# M0_Express_eh_shield.net
KiCad netlist of a schematic drawn in EAGLE
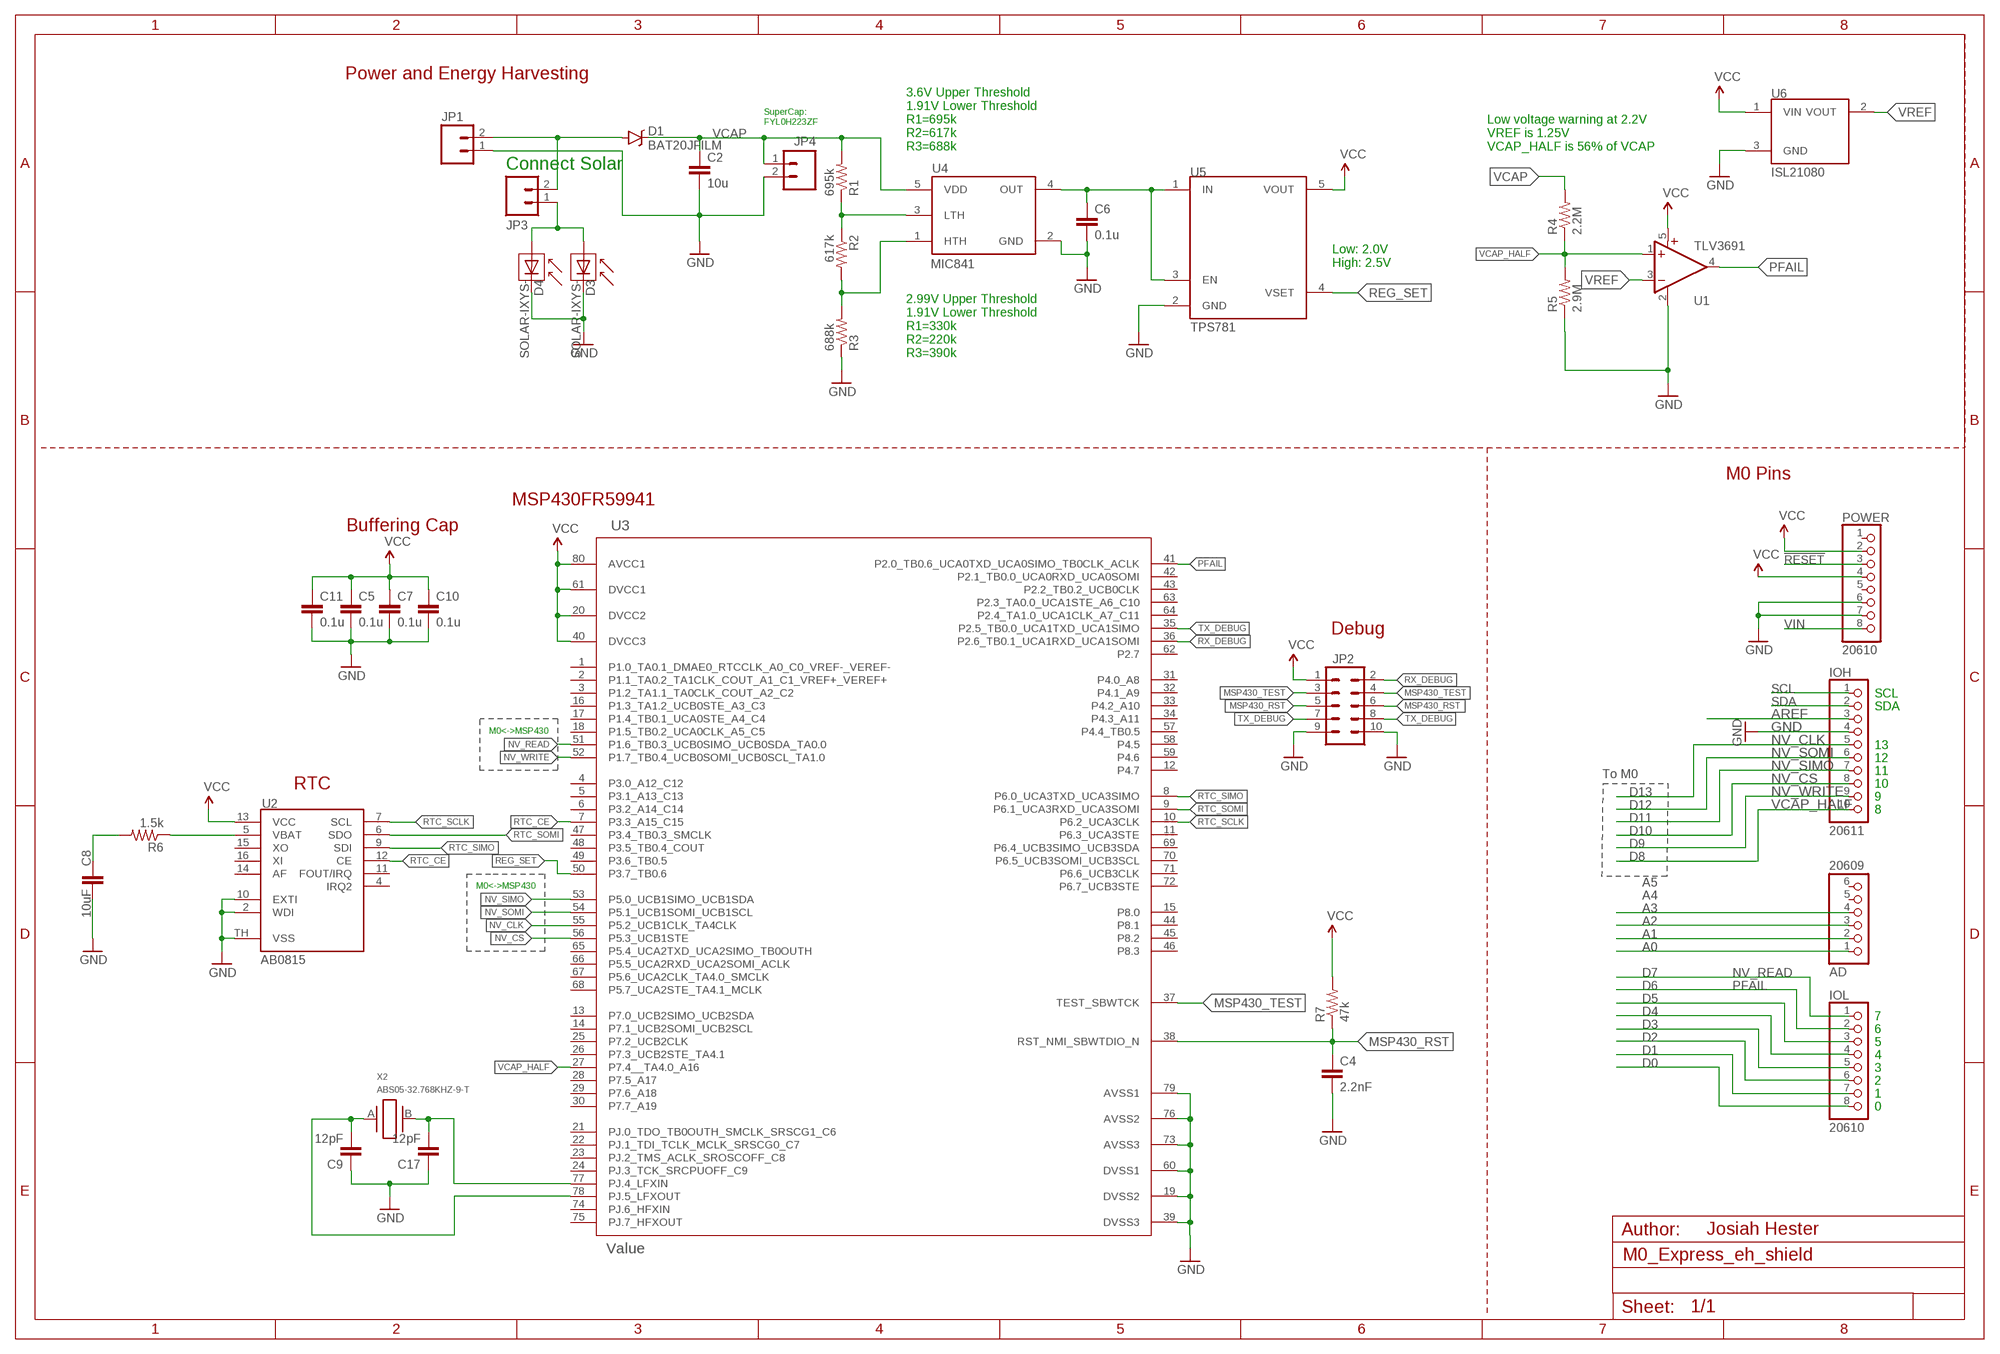
[diagram p0: schematic, sheet 1]

(export (version "E")
  (design (tool "Eeschema 10.0.6"))
  (components
    (comp (ref "AD")
      (value "20609")
      (footprint "eagle-import:1X06_OVALWAVE")
      (libsource (lib "eagle-import") (part "HEADER-1X6OVALWAVE"))
    )
    (comp (ref "C2")
      (value "10u")
      (footprint "eagle-import:0805")
      (libsource (lib "eagle-import") (part "CAP0805"))
    )
    (comp (ref "C4")
      (value "2.2nF")
      (footprint "eagle-import:0603")
      (fields (field (name "MPN") "  06035C222KAT2A"))
      (libsource (lib "eagle-import") (part "C-EU0603"))
    )
    (comp (ref "C5")
      (value "0.1u")
      (footprint "eagle-import:0603")
      (fields (field (name "MPN") "  06035C222KAT2A"))
      (libsource (lib "eagle-import") (part "C-EU0603"))
    )
    (comp (ref "C6")
      (value "0.1u")
      (footprint "eagle-import:0603")
      (fields (field (name "MPN") "  06035C222KAT2A"))
      (libsource (lib "eagle-import") (part "C-EU0603"))
    )
    (comp (ref "C7")
      (value "0.1u")
      (footprint "eagle-import:0603")
      (fields (field (name "MPN") "  06035C222KAT2A"))
      (libsource (lib "eagle-import") (part "C-EU0603"))
    )
    (comp (ref "C8")
      (value "10uF")
      (footprint "eagle-import:0805")
      (fields (field (name "MPN") "0805YD106KAT2A"))
      (libsource (lib "eagle-import") (part "CAP0805"))
    )
    (comp (ref "C9")
      (value "12pF")
      (footprint "eagle-import:0603")
      (fields (field (name "MPN") "CL10C120JB8NNNC"))
      (libsource (lib "eagle-import") (part "C-EU0603"))
    )
    (comp (ref "C10")
      (value "0.1u")
      (footprint "eagle-import:0603")
      (fields (field (name "MPN") "  06035C222KAT2A"))
      (libsource (lib "eagle-import") (part "C-EU0603"))
    )
    (comp (ref "C11")
      (value "0.1u")
      (footprint "eagle-import:0603")
      (fields (field (name "MPN") "  06035C222KAT2A"))
      (libsource (lib "eagle-import") (part "C-EU0603"))
    )
    (comp (ref "C17")
      (value "12pF")
      (footprint "eagle-import:0603")
      (fields (field (name "MPN") "CL10C120JB8NNNC"))
      (libsource (lib "eagle-import") (part "C-EU0603"))
    )
    (comp (ref "D1")
      (value "BAT20JFILM")
      (footprint "eagle-import:SOD-323")
      (libsource (lib "eagle-import") (part "BAT20JFILM"))
    )
    (comp (ref "D3")
      (value "SOLAR-IXYS-")
      (footprint "eagle-import:SOLARBIT-12X1")
      (libsource (lib "eagle-import") (part "SOLAR-IXYS-"))
    )
    (comp (ref "D4")
      (value "SOLAR-IXYS-")
      (footprint "eagle-import:SOLARBIT-12X1")
      (libsource (lib "eagle-import") (part "SOLAR-IXYS-"))
    )
    (comp (ref "IOH")
      (value "20611")
      (footprint "eagle-import:1X10_OVALWAVE")
      (libsource (lib "eagle-import") (part "HEADER-1X10OVALWAVE"))
    )
    (comp (ref "IOL")
      (value "20610")
      (footprint "eagle-import:1X08_OVALWAVE")
      (libsource (lib "eagle-import") (part "HEADER-1X8OVALWAVE"))
    )
    (comp (ref "JP1")
      (value "M02LOCK")
      (footprint "eagle-import:1X02_LOCK")
      (libsource (lib "eagle-import") (part "M02LOCK"))
    )
    (comp (ref "JP2")
      (value "M05X21.27MM")
      (footprint "eagle-import:2X5_1.27MM")
      (libsource (lib "eagle-import") (part "M05X21.27MM"))
    )
    (comp (ref "JP3")
      (value "M02LOCK")
      (footprint "eagle-import:1X02_LOCK")
      (libsource (lib "eagle-import") (part "M02LOCK"))
    )
    (comp (ref "JP4")
      (value "M025MM")
      (footprint "eagle-import:SCREWTERMINAL-5MM-2")
      (libsource (lib "eagle-import") (part "M025MM"))
    )
    (comp (ref "POWER")
      (value "20610")
      (footprint "eagle-import:1X08_OVALWAVE")
      (libsource (lib "eagle-import") (part "HEADER-1X8OVALWAVE"))
    )
    (comp (ref "R1")
      (value "695k")
      (footprint "eagle-import:0603")
      (fields (field (name "MANUFACTURERPARTNUMBER") "RC0603FR-07316KL "))
      (libsource (lib "eagle-import") (part "R-EU0603"))
    )
    (comp (ref "R2")
      (value "617k")
      (footprint "eagle-import:0603")
      (fields (field (name "MANUFACTURERPARTNUMBER") "RC0603FR-07191KL "))
      (libsource (lib "eagle-import") (part "R-EU0603"))
    )
    (comp (ref "R3")
      (value "688k")
      (footprint "eagle-import:0603")
      (fields (field (name "MANUFACTURERPARTNUMBER") "RC0603FR-07499KL"))
      (libsource (lib "eagle-import") (part "R-EU0603"))
    )
    (comp (ref "R4")
      (value "2.2M")
      (footprint "eagle-import:0603")
      (libsource (lib "eagle-import") (part "R-EU0603"))
    )
    (comp (ref "R5")
      (value "2.9M")
      (footprint "eagle-import:0603")
      (libsource (lib "eagle-import") (part "R-EU0603"))
    )
    (comp (ref "R6")
      (value "1.5k")
      (footprint "eagle-import:0603")
      (fields (field (name "MPN") "  CRCW060347K0JNEA"))
      (libsource (lib "eagle-import") (part "R-EU0603"))
    )
    (comp (ref "R7")
      (value "47k")
      (footprint "eagle-import:0603")
      (fields (field (name "MPN") "  CRCW060347K0JNEA"))
      (libsource (lib "eagle-import") (part "R-EU0603"))
    )
    (comp (ref "U1")
      (value "TLV3691")
      (footprint "eagle-import:SC70-5")
      (libsource (lib "eagle-import") (part "TLV3691"))
    )
    (comp (ref "U2")
      (value "AB0815")
      (footprint "eagle-import:QFN16")
      (fields (field (name "MPN") "AB0815-T3"))
      (libsource (lib "eagle-import") (part "AB0815"))
    )
    (comp (ref "U3")
      (value "Value")
      (footprint "eagle-import:PN0080A_N")
      (fields
        (field (name "MANUFACTURER") "Texas Instruments")
        (field (name "PARTNUMBER") "MSP430FR5994IPNR")
      )
      (libsource (lib "eagle-import") (part "MSP430FR5994IPNR"))
    )
    (comp (ref "U4")
      (value "MIC841")
      (footprint "eagle-import:SC70-5")
      (fields (field (name "MPN") "MIC841HYC5-TR"))
      (libsource (lib "eagle-import") (part "MIC841"))
    )
    (comp (ref "U5")
      (value "TPS781")
      (footprint "eagle-import:DCK_R-PDSO-G5")
      (libsource (lib "eagle-import") (part "TPS781"))
    )
    (comp (ref "U6")
      (value "ISL21080")
      (footprint "eagle-import:SOT-23")
      (libsource (lib "eagle-import") (part "ISL21080"))
    )
    (comp (ref "X2")
      (value "ABS05-32.768KHZ-9-T")
      (footprint "eagle-import:ABS05")
      (fields (field (name "MPN") "ABS05-32.768KHZ-9-T "))
      (libsource (lib "eagle-import") (part "ABS05-32.768KHZ-9-T"))
    )
  )
  (nets
    (net (code "1") (name "/A0") (class "Default")
      (node (ref "AD") (pin "1") (pinfunction "1_1") (pintype "passive"))
    )
    (net (code "2") (name "/A1") (class "Default")
      (node (ref "AD") (pin "2") (pinfunction "2_2") (pintype "passive"))
    )
    (net (code "3") (name "/A2") (class "Default")
      (node (ref "AD") (pin "3") (pinfunction "3_3") (pintype "passive"))
    )
    (net (code "4") (name "/A3") (class "Default")
      (node (ref "AD") (pin "4") (pinfunction "4_4") (pintype "passive"))
    )
    (net (code "5") (name "/AREF") (class "Default")
      (node (ref "IOH") (pin "3") (pinfunction "3_3") (pintype "passive"))
    )
    (net (code "6") (name "/D0") (class "Default")
      (node (ref "IOL") (pin "8") (pinfunction "8_8") (pintype "passive"))
    )
    (net (code "7") (name "/D1") (class "Default")
      (node (ref "IOL") (pin "7") (pinfunction "7_7") (pintype "passive"))
    )
    (net (code "8") (name "/D2") (class "Default")
      (node (ref "IOL") (pin "6") (pinfunction "6_6") (pintype "passive"))
    )
    (net (code "9") (name "/D3") (class "Default")
      (node (ref "IOL") (pin "5") (pinfunction "5_5") (pintype "passive"))
    )
    (net (code "10") (name "/D4") (class "Default")
      (node (ref "IOL") (pin "4") (pinfunction "4_4") (pintype "passive"))
    )
    (net (code "11") (name "/D5") (class "Default")
      (node (ref "IOL") (pin "3") (pinfunction "3_3") (pintype "passive"))
    )
    (net (code "12") (name "/SCL") (class "Default")
      (node (ref "IOH") (pin "1") (pinfunction "1_1") (pintype "passive"))
    )
    (net (code "13") (name "/SDA") (class "Default")
      (node (ref "IOH") (pin "2") (pinfunction "2_2") (pintype "passive"))
    )
    (net (code "14") (name "/VIN") (class "Default")
      (node (ref "POWER") (pin "8") (pinfunction "8_8") (pintype "passive"))
    )
    (net (code "15") (name "/~{RESET}") (class "Default")
      (node (ref "POWER") (pin "3") (pinfunction "3_3") (pintype "passive"))
    )
    (net (code "16") (name "GND") (class "Default")
      (node (ref "C10") (pin "2") (pinfunction "2_2") (pintype "passive"))
      (node (ref "C11") (pin "2") (pinfunction "2_2") (pintype "passive"))
      (node (ref "C17") (pin "1") (pinfunction "1_1") (pintype "passive"))
      (node (ref "C2") (pin "2") (pinfunction "2_2") (pintype "passive"))
      (node (ref "C4") (pin "2") (pinfunction "2_2") (pintype "passive"))
      (node (ref "C5") (pin "2") (pinfunction "2_2") (pintype "passive"))
      (node (ref "C6") (pin "2") (pinfunction "2_2") (pintype "passive"))
      (node (ref "C7") (pin "2") (pinfunction "2_2") (pintype "passive"))
      (node (ref "C8") (pin "2") (pinfunction "2_2") (pintype "passive"))
      (node (ref "C9") (pin "1") (pinfunction "1_1") (pintype "passive"))
      (node (ref "D3") (pin "-") (pinfunction "C_-") (pintype "passive"))
      (node (ref "D4") (pin "-") (pinfunction "C_-") (pintype "passive"))
      (node (ref "IOH") (pin "4") (pinfunction "4_4") (pintype "passive"))
      (node (ref "JP1") (pin "1") (pinfunction "1_1") (pintype "passive"))
      (node (ref "JP2") (pin "10") (pinfunction "10_10") (pintype "passive"))
      (node (ref "JP2") (pin "9") (pinfunction "9_9") (pintype "passive"))
      (node (ref "JP4") (pin "2") (pinfunction "2_2") (pintype "passive"))
      (node (ref "POWER") (pin "6") (pinfunction "6_6") (pintype "passive"))
      (node (ref "POWER") (pin "7") (pinfunction "7_7") (pintype "passive"))
      (node (ref "R3") (pin "1") (pinfunction "1_1") (pintype "passive"))
      (node (ref "R5") (pin "1") (pinfunction "1_1") (pintype "passive"))
      (node (ref "U1") (pin "2") (pinfunction "GND_2") (pintype "power_in"))
      (node (ref "U2") (pin "10") (pinfunction "EXTI_10") (pintype "bidirectional"))
      (node (ref "U2") (pin "2") (pinfunction "WDI_2") (pintype "bidirectional"))
      (node (ref "U2") (pin "TH") (pinfunction "VSS_TH") (pintype "bidirectional"))
      (node (ref "U3") (pin "19") (pinfunction "DVSS2_19") (pintype "power_in"))
      (node (ref "U3") (pin "39") (pinfunction "DVSS3_39") (pintype "power_in"))
      (node (ref "U3") (pin "60") (pinfunction "DVSS1_60") (pintype "power_in"))
      (node (ref "U3") (pin "73") (pinfunction "AVSS3_73") (pintype "power_in"))
      (node (ref "U3") (pin "76") (pinfunction "AVSS2_76") (pintype "power_in"))
      (node (ref "U3") (pin "79") (pinfunction "AVSS1_79") (pintype "power_in"))
      (node (ref "U4") (pin "2") (pinfunction "GND_2") (pintype "bidirectional"))
      (node (ref "U5") (pin "2") (pinfunction "GND_2") (pintype "bidirectional"))
      (node (ref "U6") (pin "3") (pinfunction "GND_3") (pintype "bidirectional"))
    )
    (net (code "17") (name "MSP430_RST") (class "Default")
      (node (ref "C4") (pin "1") (pinfunction "1_1") (pintype "passive"))
      (node (ref "JP2") (pin "5") (pinfunction "5_5") (pintype "passive"))
      (node (ref "JP2") (pin "6") (pinfunction "6_6") (pintype "passive"))
      (node (ref "R7") (pin "1") (pinfunction "1_1") (pintype "passive"))
      (node (ref "U3") (pin "38") (pinfunction "RST_NMI_SBWTDIO_N_38") (pintype "bidirectional"))
    )
    (net (code "18") (name "MSP430_TEST") (class "Default")
      (node (ref "JP2") (pin "3") (pinfunction "3_3") (pintype "passive"))
      (node (ref "JP2") (pin "4") (pinfunction "4_4") (pintype "passive"))
      (node (ref "U3") (pin "37") (pinfunction "TEST_SBWTCK_37") (pintype "input"))
    )
    (net (code "19") (name "NV_CLK") (class "Default")
      (node (ref "IOH") (pin "5") (pinfunction "5_5") (pintype "passive"))
      (node (ref "U3") (pin "55") (pinfunction "P5.2_UCB1CLK_TA4CLK_55") (pintype "bidirectional"))
    )
    (net (code "20") (name "NV_CS") (class "Default")
      (node (ref "IOH") (pin "8") (pinfunction "8_8") (pintype "passive"))
      (node (ref "U3") (pin "56") (pinfunction "P5.3_UCB1STE_56") (pintype "bidirectional"))
    )
    (net (code "21") (name "NV_READ") (class "Default")
      (node (ref "IOL") (pin "1") (pinfunction "1_1") (pintype "passive"))
      (node (ref "U3") (pin "51") (pinfunction "P1.6_TB0.3_UCB0SIMO_UCB0SDA_TA0.0_51") (pintype "bidirectional"))
    )
    (net (code "22") (name "NV_SIMO") (class "Default")
      (node (ref "IOH") (pin "7") (pinfunction "7_7") (pintype "passive"))
      (node (ref "U3") (pin "53") (pinfunction "P5.0_UCB1SIMO_UCB1SDA_53") (pintype "bidirectional"))
    )
    (net (code "23") (name "NV_SOMI") (class "Default")
      (node (ref "IOH") (pin "6") (pinfunction "6_6") (pintype "passive"))
      (node (ref "U3") (pin "54") (pinfunction "P5.1_UCB1SOMI_UCB1SCL_54") (pintype "bidirectional"))
    )
    (net (code "24") (name "NV_WRITE") (class "Default")
      (node (ref "IOH") (pin "9") (pinfunction "9_9") (pintype "passive"))
      (node (ref "U3") (pin "52") (pinfunction "P1.7_TB0.4_UCB0SOMI_UCB0SCL_TA1.0_52") (pintype "bidirectional"))
    )
    (net (code "25") (name "Net-(C8-Pad1)") (class "Default")
      (node (ref "C8") (pin "1") (pinfunction "1_1") (pintype "passive"))
      (node (ref "R6") (pin "2") (pinfunction "2_2") (pintype "passive"))
    )
    (net (code "26") (name "Net-(D1-PadA)") (class "Default")
      (node (ref "D1") (pin "A") (pinfunction "A_A") (pintype "passive"))
      (node (ref "JP1") (pin "2") (pinfunction "2_2") (pintype "passive"))
      (node (ref "JP3") (pin "2") (pinfunction "2_2") (pintype "passive"))
    )
    (net (code "27") (name "Net-(D3-A)") (class "Default")
      (node (ref "D3") (pin "+") (pinfunction "A_+") (pintype "passive"))
      (node (ref "D4") (pin "+") (pinfunction "A_+") (pintype "passive"))
      (node (ref "JP3") (pin "1") (pinfunction "1_1") (pintype "passive"))
    )
    (net (code "28") (name "Net-(U2-VBAT)") (class "Default")
      (node (ref "R6") (pin "1") (pinfunction "1_1") (pintype "passive"))
      (node (ref "U2") (pin "5") (pinfunction "VBAT_5") (pintype "bidirectional"))
    )
    (net (code "29") (name "Net-(U3-PJ.4_LFXIN)") (class "Default")
      (node (ref "C17") (pin "2") (pinfunction "2_2") (pintype "passive"))
      (node (ref "U3") (pin "77") (pinfunction "PJ.4_LFXIN_77") (pintype "bidirectional"))
      (node (ref "X2") (pin "B") (pinfunction "2_B") (pintype "bidirectional"))
    )
    (net (code "30") (name "Net-(U3-PJ.5_LFXOUT)") (class "Default")
      (node (ref "C9") (pin "2") (pinfunction "2_2") (pintype "passive"))
      (node (ref "U3") (pin "78") (pinfunction "PJ.5_LFXOUT_78") (pintype "bidirectional"))
      (node (ref "X2") (pin "A") (pinfunction "1_A") (pintype "bidirectional"))
    )
    (net (code "31") (name "Net-(U4-HTH)") (class "Default")
      (node (ref "R2") (pin "2") (pinfunction "2_2") (pintype "passive"))
      (node (ref "R3") (pin "2") (pinfunction "2_2") (pintype "passive"))
      (node (ref "U4") (pin "1") (pinfunction "HTH_1") (pintype "bidirectional"))
    )
    (net (code "32") (name "Net-(U4-LTH)") (class "Default")
      (node (ref "R1") (pin "1") (pinfunction "1_1") (pintype "passive"))
      (node (ref "R2") (pin "1") (pinfunction "1_1") (pintype "passive"))
      (node (ref "U4") (pin "3") (pinfunction "LTH_3") (pintype "bidirectional"))
    )
    (net (code "33") (name "Net-(U4-OUT)") (class "Default")
      (node (ref "C6") (pin "1") (pinfunction "1_1") (pintype "passive"))
      (node (ref "U4") (pin "4") (pinfunction "OUT_4") (pintype "bidirectional"))
      (node (ref "U5") (pin "1") (pinfunction "IN_1") (pintype "bidirectional"))
      (node (ref "U5") (pin "3") (pinfunction "EN_3") (pintype "bidirectional"))
    )
    (net (code "34") (name "PFAIL") (class "Default")
      (node (ref "IOL") (pin "2") (pinfunction "2_2") (pintype "passive"))
      (node (ref "U1") (pin "4") (pinfunction "OUT_4") (pintype "output"))
      (node (ref "U3") (pin "41") (pinfunction "P2.0_TB0.6_UCA0TXD_UCA0SIMO_TB0CLK_ACLK_41") (pintype "bidirectional"))
    )
    (net (code "35") (name "REG_SET") (class "Default")
      (node (ref "U3") (pin "50") (pinfunction "P3.7_TB0.6_50") (pintype "bidirectional"))
      (node (ref "U5") (pin "4") (pinfunction "VSET_4") (pintype "bidirectional"))
    )
    (net (code "36") (name "RTC_CE") (class "Default")
      (node (ref "U2") (pin "12") (pinfunction "CE_12") (pintype "bidirectional"))
      (node (ref "U3") (pin "7") (pinfunction "P3.3_A15_C15_7") (pintype "bidirectional"))
    )
    (net (code "37") (name "RTC_SCLK") (class "Default")
      (node (ref "U2") (pin "7") (pinfunction "SCL_7") (pintype "bidirectional"))
      (node (ref "U3") (pin "10") (pinfunction "P6.2_UCA3CLK_10") (pintype "bidirectional"))
    )
    (net (code "38") (name "RTC_SIMO") (class "Default")
      (node (ref "U2") (pin "9") (pinfunction "SDI_9") (pintype "bidirectional"))
      (node (ref "U3") (pin "8") (pinfunction "P6.0_UCA3TXD_UCA3SIMO_8") (pintype "bidirectional"))
    )
    (net (code "39") (name "RTC_SOMI") (class "Default")
      (node (ref "U2") (pin "6") (pinfunction "SDO_6") (pintype "bidirectional"))
      (node (ref "U3") (pin "9") (pinfunction "P6.1_UCA3RXD_UCA3SOMI_9") (pintype "bidirectional"))
    )
    (net (code "40") (name "RX_DEBUG") (class "Default")
      (node (ref "JP2") (pin "2") (pinfunction "2_2") (pintype "passive"))
      (node (ref "U3") (pin "36") (pinfunction "P2.6_TB0.1_UCA1RXD_UCA1SOMI_36") (pintype "bidirectional"))
    )
    (net (code "41") (name "TX_DEBUG") (class "Default")
      (node (ref "JP2") (pin "7") (pinfunction "7_7") (pintype "passive"))
      (node (ref "JP2") (pin "8") (pinfunction "8_8") (pintype "passive"))
      (node (ref "U3") (pin "35") (pinfunction "P2.5_TB0.0_UCA1TXD_UCA1SIMO_35") (pintype "bidirectional"))
    )
    (net (code "42") (name "VCAP") (class "Default")
      (node (ref "C2") (pin "1") (pinfunction "1_1") (pintype "passive"))
      (node (ref "D1") (pin "C") (pinfunction "C_C") (pintype "passive"))
      (node (ref "JP4") (pin "1") (pinfunction "1_1") (pintype "passive"))
      (node (ref "R1") (pin "2") (pinfunction "2_2") (pintype "passive"))
      (node (ref "R4") (pin "2") (pinfunction "2_2") (pintype "passive"))
      (node (ref "U4") (pin "5") (pinfunction "VDD_5") (pintype "bidirectional"))
    )
    (net (code "43") (name "VCAP_HALF") (class "Default")
      (node (ref "IOH") (pin "10") (pinfunction "10_10") (pintype "passive"))
      (node (ref "R4") (pin "1") (pinfunction "1_1") (pintype "passive"))
      (node (ref "R5") (pin "2") (pinfunction "2_2") (pintype "passive"))
      (node (ref "U1") (pin "1") (pinfunction "+IN_1") (pintype "input"))
      (node (ref "U3") (pin "27") (pinfunction "P7.4__TA4.0_A16_27") (pintype "bidirectional"))
    )
    (net (code "44") (name "VCC") (class "Default")
      (node (ref "C10") (pin "1") (pinfunction "1_1") (pintype "passive"))
      (node (ref "C11") (pin "1") (pinfunction "1_1") (pintype "passive"))
      (node (ref "C5") (pin "1") (pinfunction "1_1") (pintype "passive"))
      (node (ref "C7") (pin "1") (pinfunction "1_1") (pintype "passive"))
      (node (ref "JP2") (pin "1") (pinfunction "1_1") (pintype "passive"))
      (node (ref "POWER") (pin "2") (pinfunction "2_2") (pintype "passive"))
      (node (ref "POWER") (pin "4") (pinfunction "4_4") (pintype "passive"))
      (node (ref "R7") (pin "2") (pinfunction "2_2") (pintype "passive"))
      (node (ref "U1") (pin "5") (pinfunction "V+_5") (pintype "power_in"))
      (node (ref "U2") (pin "13") (pinfunction "VCC_13") (pintype "bidirectional"))
      (node (ref "U3") (pin "20") (pinfunction "DVCC2_20") (pintype "power_in"))
      (node (ref "U3") (pin "40") (pinfunction "DVCC3_40") (pintype "power_in"))
      (node (ref "U3") (pin "61") (pinfunction "DVCC1_61") (pintype "power_in"))
      (node (ref "U3") (pin "80") (pinfunction "AVCC1_80") (pintype "power_in"))
      (node (ref "U5") (pin "5") (pinfunction "VOUT_5") (pintype "bidirectional"))
      (node (ref "U6") (pin "1") (pinfunction "VIN_1") (pintype "bidirectional"))
    )
    (net (code "45") (name "VREF") (class "Default")
      (node (ref "U1") (pin "3") (pinfunction "-IN_3") (pintype "input"))
      (node (ref "U6") (pin "2") (pinfunction "VOUT_2") (pintype "bidirectional"))
    )
    (net (code "46") (name "unconnected-(AD-Pad5)") (class "Default")
      (node (ref "AD") (pin "5") (pinfunction "5_5") (pintype "passive"))
    )
    (net (code "47") (name "unconnected-(AD-Pad6)") (class "Default")
      (node (ref "AD") (pin "6") (pinfunction "6_6") (pintype "passive"))
    )
    (net (code "48") (name "unconnected-(POWER-Pad1)") (class "Default")
      (node (ref "POWER") (pin "1") (pinfunction "1_1") (pintype "passive"))
    )
    (net (code "49") (name "unconnected-(POWER-Pad5)") (class "Default")
      (node (ref "POWER") (pin "5") (pinfunction "5_5") (pintype "passive"))
    )
    (net (code "50") (name "unconnected-(U2-AF-Pad14)") (class "Default")
      (node (ref "U2") (pin "14") (pinfunction "AF_14") (pintype "bidirectional"))
    )
    (net (code "51") (name "unconnected-(U2-FOUT{slash}IRQ-Pad11)") (class "Default")
      (node (ref "U2") (pin "11") (pinfunction "FOUT/IRQ_11") (pintype "bidirectional"))
    )
    (net (code "52") (name "unconnected-(U2-IRQ2-Pad4)") (class "Default")
      (node (ref "U2") (pin "4") (pinfunction "IRQ2_4") (pintype "bidirectional"))
    )
    (net (code "53") (name "unconnected-(U2-XI-Pad16)") (class "Default")
      (node (ref "U2") (pin "16") (pinfunction "XI_16") (pintype "bidirectional"))
    )
    (net (code "54") (name "unconnected-(U2-XO-Pad15)") (class "Default")
      (node (ref "U2") (pin "15") (pinfunction "XO_15") (pintype "bidirectional"))
    )
    (net (code "55") (name "unconnected-(U3-P1.0_TA0.1_DMAE0_RTCCLK_A0_C0_VREF-_VEREF--Pad1)") (class "Default")
      (node (ref "U3") (pin "1") (pinfunction "P1.0_TA0.1_DMAE0_RTCCLK_A0_C0_VREF-_VEREF-_1") (pintype "bidirectional"))
    )
    (net (code "56") (name "unconnected-(U3-P1.1_TA0.2_TA1CLK_COUT_A1_C1_VREF+_VEREF+-Pad2)") (class "Default")
      (node (ref "U3") (pin "2") (pinfunction "P1.1_TA0.2_TA1CLK_COUT_A1_C1_VREF+_VEREF+_2") (pintype "bidirectional"))
    )
    (net (code "57") (name "unconnected-(U3-P1.2_TA1.1_TA0CLK_COUT_A2_C2-Pad3)") (class "Default")
      (node (ref "U3") (pin "3") (pinfunction "P1.2_TA1.1_TA0CLK_COUT_A2_C2_3") (pintype "bidirectional"))
    )
    (net (code "58") (name "unconnected-(U3-P1.3_TA1.2_UCB0STE_A3_C3-Pad16)") (class "Default")
      (node (ref "U3") (pin "16") (pinfunction "P1.3_TA1.2_UCB0STE_A3_C3_16") (pintype "bidirectional"))
    )
    (net (code "59") (name "unconnected-(U3-P1.4_TB0.1_UCA0STE_A4_C4-Pad17)") (class "Default")
      (node (ref "U3") (pin "17") (pinfunction "P1.4_TB0.1_UCA0STE_A4_C4_17") (pintype "bidirectional"))
    )
    (net (code "60") (name "unconnected-(U3-P1.5_TB0.2_UCA0CLK_A5_C5-Pad18)") (class "Default")
      (node (ref "U3") (pin "18") (pinfunction "P1.5_TB0.2_UCA0CLK_A5_C5_18") (pintype "bidirectional"))
    )
    (net (code "61") (name "unconnected-(U3-P2.1_TB0.0_UCA0RXD_UCA0SOMI-Pad42)") (class "Default")
      (node (ref "U3") (pin "42") (pinfunction "P2.1_TB0.0_UCA0RXD_UCA0SOMI_42") (pintype "bidirectional"))
    )
    (net (code "62") (name "unconnected-(U3-P2.2_TB0.2_UCB0CLK-Pad43)") (class "Default")
      (node (ref "U3") (pin "43") (pinfunction "P2.2_TB0.2_UCB0CLK_43") (pintype "bidirectional"))
    )
    (net (code "63") (name "unconnected-(U3-P2.3_TA0.0_UCA1STE_A6_C10-Pad63)") (class "Default")
      (node (ref "U3") (pin "63") (pinfunction "P2.3_TA0.0_UCA1STE_A6_C10_63") (pintype "bidirectional"))
    )
    (net (code "64") (name "unconnected-(U3-P2.4_TA1.0_UCA1CLK_A7_C11-Pad64)") (class "Default")
      (node (ref "U3") (pin "64") (pinfunction "P2.4_TA1.0_UCA1CLK_A7_C11_64") (pintype "bidirectional"))
    )
    (net (code "65") (name "unconnected-(U3-P2.7-Pad62)") (class "Default")
      (node (ref "U3") (pin "62") (pinfunction "P2.7_62") (pintype "bidirectional"))
    )
    (net (code "66") (name "unconnected-(U3-P3.0_A12_C12-Pad4)") (class "Default")
      (node (ref "U3") (pin "4") (pinfunction "P3.0_A12_C12_4") (pintype "bidirectional"))
    )
    (net (code "67") (name "unconnected-(U3-P3.1_A13_C13-Pad5)") (class "Default")
      (node (ref "U3") (pin "5") (pinfunction "P3.1_A13_C13_5") (pintype "bidirectional"))
    )
    (net (code "68") (name "unconnected-(U3-P3.2_A14_C14-Pad6)") (class "Default")
      (node (ref "U3") (pin "6") (pinfunction "P3.2_A14_C14_6") (pintype "bidirectional"))
    )
    (net (code "69") (name "unconnected-(U3-P3.4_TB0.3_SMCLK-Pad47)") (class "Default")
      (node (ref "U3") (pin "47") (pinfunction "P3.4_TB0.3_SMCLK_47") (pintype "bidirectional"))
    )
    (net (code "70") (name "unconnected-(U3-P3.5_TB0.4_COUT-Pad48)") (class "Default")
      (node (ref "U3") (pin "48") (pinfunction "P3.5_TB0.4_COUT_48") (pintype "bidirectional"))
    )
    (net (code "71") (name "unconnected-(U3-P3.6_TB0.5-Pad49)") (class "Default")
      (node (ref "U3") (pin "49") (pinfunction "P3.6_TB0.5_49") (pintype "bidirectional"))
    )
    (net (code "72") (name "unconnected-(U3-P4.0_A8-Pad31)") (class "Default")
      (node (ref "U3") (pin "31") (pinfunction "P4.0_A8_31") (pintype "bidirectional"))
    )
    (net (code "73") (name "unconnected-(U3-P4.1_A9-Pad32)") (class "Default")
      (node (ref "U3") (pin "32") (pinfunction "P4.1_A9_32") (pintype "bidirectional"))
    )
    (net (code "74") (name "unconnected-(U3-P4.2_A10-Pad33)") (class "Default")
      (node (ref "U3") (pin "33") (pinfunction "P4.2_A10_33") (pintype "bidirectional"))
    )
    (net (code "75") (name "unconnected-(U3-P4.3_A11-Pad34)") (class "Default")
      (node (ref "U3") (pin "34") (pinfunction "P4.3_A11_34") (pintype "bidirectional"))
    )
    (net (code "76") (name "unconnected-(U3-P4.4_TB0.5-Pad57)") (class "Default")
      (node (ref "U3") (pin "57") (pinfunction "P4.4_TB0.5_57") (pintype "bidirectional"))
    )
    (net (code "77") (name "unconnected-(U3-P4.5-Pad58)") (class "Default")
      (node (ref "U3") (pin "58") (pinfunction "P4.5_58") (pintype "bidirectional"))
    )
    (net (code "78") (name "unconnected-(U3-P4.6-Pad59)") (class "Default")
      (node (ref "U3") (pin "59") (pinfunction "P4.6_59") (pintype "bidirectional"))
    )
    (net (code "79") (name "unconnected-(U3-P4.7-Pad12)") (class "Default")
      (node (ref "U3") (pin "12") (pinfunction "P4.7_12") (pintype "bidirectional"))
    )
    (net (code "80") (name "unconnected-(U3-P5.4_UCA2TXD_UCA2SIMO_TB0OUTH-Pad65)") (class "Default")
      (node (ref "U3") (pin "65") (pinfunction "P5.4_UCA2TXD_UCA2SIMO_TB0OUTH_65") (pintype "bidirectional"))
    )
    (net (code "81") (name "unconnected-(U3-P5.5_UCA2RXD_UCA2SOMI_ACLK-Pad66)") (class "Default")
      (node (ref "U3") (pin "66") (pinfunction "P5.5_UCA2RXD_UCA2SOMI_ACLK_66") (pintype "bidirectional"))
    )
    (net (code "82") (name "unconnected-(U3-P5.6_UCA2CLK_TA4.0_SMCLK-Pad67)") (class "Default")
      (node (ref "U3") (pin "67") (pinfunction "P5.6_UCA2CLK_TA4.0_SMCLK_67") (pintype "bidirectional"))
    )
    (net (code "83") (name "unconnected-(U3-P5.7_UCA2STE_TA4.1_MCLK-Pad68)") (class "Default")
      (node (ref "U3") (pin "68") (pinfunction "P5.7_UCA2STE_TA4.1_MCLK_68") (pintype "bidirectional"))
    )
    (net (code "84") (name "unconnected-(U3-P6.3_UCA3STE-Pad11)") (class "Default")
      (node (ref "U3") (pin "11") (pinfunction "P6.3_UCA3STE_11") (pintype "bidirectional"))
    )
    (net (code "85") (name "unconnected-(U3-P6.4_UCB3SIMO_UCB3SDA-Pad69)") (class "Default")
      (node (ref "U3") (pin "69") (pinfunction "P6.4_UCB3SIMO_UCB3SDA_69") (pintype "bidirectional"))
    )
    (net (code "86") (name "unconnected-(U3-P6.5_UCB3SOMI_UCB3SCL-Pad70)") (class "Default")
      (node (ref "U3") (pin "70") (pinfunction "P6.5_UCB3SOMI_UCB3SCL_70") (pintype "bidirectional"))
    )
    (net (code "87") (name "unconnected-(U3-P6.6_UCB3CLK-Pad71)") (class "Default")
      (node (ref "U3") (pin "71") (pinfunction "P6.6_UCB3CLK_71") (pintype "bidirectional"))
    )
    (net (code "88") (name "unconnected-(U3-P6.7_UCB3STE-Pad72)") (class "Default")
      (node (ref "U3") (pin "72") (pinfunction "P6.7_UCB3STE_72") (pintype "bidirectional"))
    )
    (net (code "89") (name "unconnected-(U3-P7.0_UCB2SIMO_UCB2SDA-Pad13)") (class "Default")
      (node (ref "U3") (pin "13") (pinfunction "P7.0_UCB2SIMO_UCB2SDA_13") (pintype "bidirectional"))
    )
    (net (code "90") (name "unconnected-(U3-P7.1_UCB2SOMI_UCB2SCL-Pad14)") (class "Default")
      (node (ref "U3") (pin "14") (pinfunction "P7.1_UCB2SOMI_UCB2SCL_14") (pintype "bidirectional"))
    )
    (net (code "91") (name "unconnected-(U3-P7.2_UCB2CLK-Pad25)") (class "Default")
      (node (ref "U3") (pin "25") (pinfunction "P7.2_UCB2CLK_25") (pintype "bidirectional"))
    )
    (net (code "92") (name "unconnected-(U3-P7.3_UCB2STE_TA4.1-Pad26)") (class "Default")
      (node (ref "U3") (pin "26") (pinfunction "P7.3_UCB2STE_TA4.1_26") (pintype "bidirectional"))
    )
    (net (code "93") (name "unconnected-(U3-P7.5_A17-Pad28)") (class "Default")
      (node (ref "U3") (pin "28") (pinfunction "P7.5_A17_28") (pintype "bidirectional"))
    )
    (net (code "94") (name "unconnected-(U3-P7.6_A18-Pad29)") (class "Default")
      (node (ref "U3") (pin "29") (pinfunction "P7.6_A18_29") (pintype "bidirectional"))
    )
    (net (code "95") (name "unconnected-(U3-P7.7_A19-Pad30)") (class "Default")
      (node (ref "U3") (pin "30") (pinfunction "P7.7_A19_30") (pintype "bidirectional"))
    )
    (net (code "96") (name "unconnected-(U3-P8.0-Pad15)") (class "Default")
      (node (ref "U3") (pin "15") (pinfunction "P8.0_15") (pintype "bidirectional"))
    )
    (net (code "97") (name "unconnected-(U3-P8.1-Pad44)") (class "Default")
      (node (ref "U3") (pin "44") (pinfunction "P8.1_44") (pintype "bidirectional"))
    )
    (net (code "98") (name "unconnected-(U3-P8.2-Pad45)") (class "Default")
      (node (ref "U3") (pin "45") (pinfunction "P8.2_45") (pintype "bidirectional"))
    )
    (net (code "99") (name "unconnected-(U3-P8.3-Pad46)") (class "Default")
      (node (ref "U3") (pin "46") (pinfunction "P8.3_46") (pintype "bidirectional"))
    )
    (net (code "100") (name "unconnected-(U3-PJ.0_TDO_TB0OUTH_SMCLK_SRSCG1_C6-Pad21)") (class "Default")
      (node (ref "U3") (pin "21") (pinfunction "PJ.0_TDO_TB0OUTH_SMCLK_SRSCG1_C6_21") (pintype "bidirectional"))
    )
    (net (code "101") (name "unconnected-(U3-PJ.1_TDI_TCLK_MCLK_SRSCG0_C7-Pad22)") (class "Default")
      (node (ref "U3") (pin "22") (pinfunction "PJ.1_TDI_TCLK_MCLK_SRSCG0_C7_22") (pintype "bidirectional"))
    )
    (net (code "102") (name "unconnected-(U3-PJ.2_TMS_ACLK_SROSCOFF_C8-Pad23)") (class "Default")
      (node (ref "U3") (pin "23") (pinfunction "PJ.2_TMS_ACLK_SROSCOFF_C8_23") (pintype "bidirectional"))
    )
    (net (code "103") (name "unconnected-(U3-PJ.3_TCK_SRCPUOFF_C9-Pad24)") (class "Default")
      (node (ref "U3") (pin "24") (pinfunction "PJ.3_TCK_SRCPUOFF_C9_24") (pintype "bidirectional"))
    )
    (net (code "104") (name "unconnected-(U3-PJ.6_HFXIN-Pad74)") (class "Default")
      (node (ref "U3") (pin "74") (pinfunction "PJ.6_HFXIN_74") (pintype "bidirectional"))
    )
    (net (code "105") (name "unconnected-(U3-PJ.7_HFXOUT-Pad75)") (class "Default")
      (node (ref "U3") (pin "75") (pinfunction "PJ.7_HFXOUT_75") (pintype "bidirectional"))
    )
  )
)
